# hdmispi.net
KiCad netlist of a schematic drawn in EAGLE
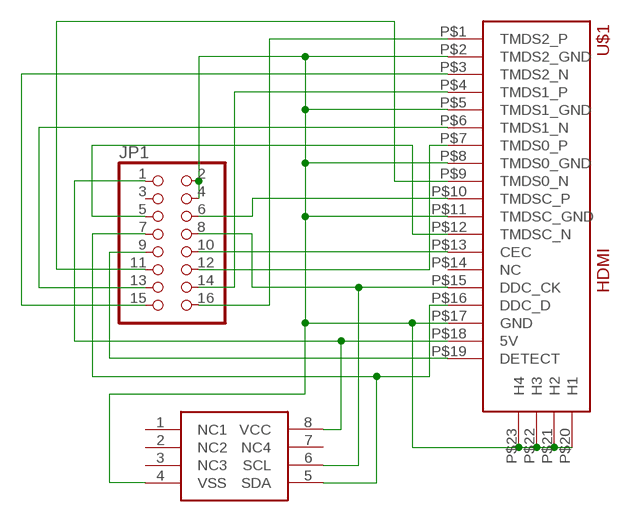
[diagram p0: schematic, sheet 1]

(export (version "E")
  (design (tool "Eeschema 10.0.6"))
  (components
    (comp (ref "JP1")
      (value "PINHD-2X8")
      (footprint "eagle-import:2X08")
      (libsource (lib "eagle-import") (part "PINHD-2X8"))
    )
    (comp (ref "U$1")
      (value "HDMI")
      (footprint "eagle-import:HDMI")
      (libsource (lib "eagle-import") (part "HDMI"))
    )
    (comp (ref "U$2")
      (value "I2CEEPROM-SOIC8")
      (footprint "eagle-import:SOIC8")
      (libsource (lib "eagle-import") (part "I2CEEPROM-SOIC8"))
    )
  )
  (nets
    (net (code "1") (name "Net-(U$1-5V)") (class "Default")
      (node (ref "JP1") (pin "1") (pinfunction "1_1") (pintype "passive"))
      (node (ref "U$1") (pin "P$18") (pinfunction "5V_P$18") (pintype "bidirectional"))
      (node (ref "U$2") (pin "8") (pinfunction "VCC_8") (pintype "bidirectional"))
    )
    (net (code "2") (name "Net-(U$1-CEC)") (class "Default")
      (node (ref "JP1") (pin "10") (pinfunction "10_10") (pintype "passive"))
      (node (ref "U$1") (pin "P$13") (pinfunction "CEC_P$13") (pintype "bidirectional"))
    )
    (net (code "3") (name "Net-(U$1-DDC_CK)") (class "Default")
      (node (ref "JP1") (pin "8") (pinfunction "8_8") (pintype "passive"))
      (node (ref "U$1") (pin "P$15") (pinfunction "DDC_CK_P$15") (pintype "bidirectional"))
      (node (ref "U$2") (pin "6") (pinfunction "SCL_6") (pintype "bidirectional"))
    )
    (net (code "4") (name "Net-(U$1-DDC_D)") (class "Default")
      (node (ref "JP1") (pin "7") (pinfunction "7_7") (pintype "passive"))
      (node (ref "U$1") (pin "P$16") (pinfunction "DDC_D_P$16") (pintype "bidirectional"))
      (node (ref "U$2") (pin "5") (pinfunction "SDA_5") (pintype "bidirectional"))
    )
    (net (code "5") (name "Net-(U$1-DETECT)") (class "Default")
      (node (ref "JP1") (pin "9") (pinfunction "9_9") (pintype "passive"))
      (node (ref "U$1") (pin "P$19") (pinfunction "DETECT_P$19") (pintype "bidirectional"))
    )
    (net (code "6") (name "Net-(U$1-GND)") (class "Default")
      (node (ref "JP1") (pin "2") (pinfunction "2_2") (pintype "passive"))
      (node (ref "JP1") (pin "4") (pinfunction "4_4") (pintype "passive"))
      (node (ref "U$1") (pin "P$11") (pinfunction "TMDSC_GND_P$11") (pintype "bidirectional"))
      (node (ref "U$1") (pin "P$17") (pinfunction "GND_P$17") (pintype "bidirectional"))
      (node (ref "U$1") (pin "P$2") (pinfunction "TMDS2_GND_P$2") (pintype "bidirectional"))
      (node (ref "U$1") (pin "P$20") (pinfunction "H1_P$20") (pintype "bidirectional"))
      (node (ref "U$1") (pin "P$21") (pinfunction "H2_P$21") (pintype "bidirectional"))
      (node (ref "U$1") (pin "P$22") (pinfunction "H3_P$22") (pintype "bidirectional"))
      (node (ref "U$1") (pin "P$23") (pinfunction "H4_P$23") (pintype "bidirectional"))
      (node (ref "U$1") (pin "P$5") (pinfunction "TMDS1_GND_P$5") (pintype "bidirectional"))
      (node (ref "U$1") (pin "P$8") (pinfunction "TMDS0_GND_P$8") (pintype "bidirectional"))
      (node (ref "U$2") (pin "4") (pinfunction "VSS_4") (pintype "bidirectional"))
    )
    (net (code "7") (name "Net-(U$1-TMDS0_N)") (class "Default")
      (node (ref "JP1") (pin "11") (pinfunction "11_11") (pintype "passive"))
      (node (ref "U$1") (pin "P$9") (pinfunction "TMDS0_N_P$9") (pintype "bidirectional"))
    )
    (net (code "8") (name "Net-(U$1-TMDS0_P)") (class "Default")
      (node (ref "JP1") (pin "12") (pinfunction "12_12") (pintype "passive"))
      (node (ref "U$1") (pin "P$7") (pinfunction "TMDS0_P_P$7") (pintype "bidirectional"))
    )
    (net (code "9") (name "Net-(U$1-TMDS1_N)") (class "Default")
      (node (ref "JP1") (pin "13") (pinfunction "13_13") (pintype "passive"))
      (node (ref "U$1") (pin "P$6") (pinfunction "TMDS1_N_P$6") (pintype "bidirectional"))
    )
    (net (code "10") (name "Net-(U$1-TMDS1_P)") (class "Default")
      (node (ref "JP1") (pin "14") (pinfunction "14_14") (pintype "passive"))
      (node (ref "U$1") (pin "P$4") (pinfunction "TMDS1_P_P$4") (pintype "bidirectional"))
    )
    (net (code "11") (name "Net-(U$1-TMDS2_N)") (class "Default")
      (node (ref "JP1") (pin "15") (pinfunction "15_15") (pintype "passive"))
      (node (ref "U$1") (pin "P$3") (pinfunction "TMDS2_N_P$3") (pintype "bidirectional"))
    )
    (net (code "12") (name "Net-(U$1-TMDS2_P)") (class "Default")
      (node (ref "JP1") (pin "16") (pinfunction "16_16") (pintype "passive"))
      (node (ref "U$1") (pin "P$1") (pinfunction "TMDS2_P_P$1") (pintype "bidirectional"))
    )
    (net (code "13") (name "Net-(U$1-TMDSC_N)") (class "Default")
      (node (ref "JP1") (pin "5") (pinfunction "5_5") (pintype "passive"))
      (node (ref "U$1") (pin "P$12") (pinfunction "TMDSC_N_P$12") (pintype "bidirectional"))
    )
    (net (code "14") (name "Net-(U$1-TMDSC_P)") (class "Default")
      (node (ref "JP1") (pin "6") (pinfunction "6_6") (pintype "passive"))
      (node (ref "U$1") (pin "P$10") (pinfunction "TMDSC_P_P$10") (pintype "bidirectional"))
    )
    (net (code "15") (name "unconnected-(JP1-Pad3)") (class "Default")
      (node (ref "JP1") (pin "3") (pinfunction "3_3") (pintype "passive"))
    )
    (net (code "16") (name "unconnected-(U$1-NC-PadP$14)") (class "Default")
      (node (ref "U$1") (pin "P$14") (pinfunction "NC_P$14") (pintype "bidirectional"))
    )
    (net (code "17") (name "unconnected-(U$2-NC1-Pad1)") (class "Default")
      (node (ref "U$2") (pin "1") (pinfunction "NC1_1") (pintype "bidirectional"))
    )
    (net (code "18") (name "unconnected-(U$2-NC2-Pad2)") (class "Default")
      (node (ref "U$2") (pin "2") (pinfunction "NC2_2") (pintype "bidirectional"))
    )
    (net (code "19") (name "unconnected-(U$2-NC3-Pad3)") (class "Default")
      (node (ref "U$2") (pin "3") (pinfunction "NC3_3") (pintype "bidirectional"))
    )
    (net (code "20") (name "unconnected-(U$2-NC4-Pad7)") (class "Default")
      (node (ref "U$2") (pin "7") (pinfunction "NC4_7") (pintype "bidirectional"))
    )
  )
)
